# lora_repeter_2.net
KiCad netlist of a schematic drawn in EasyEDA Pro
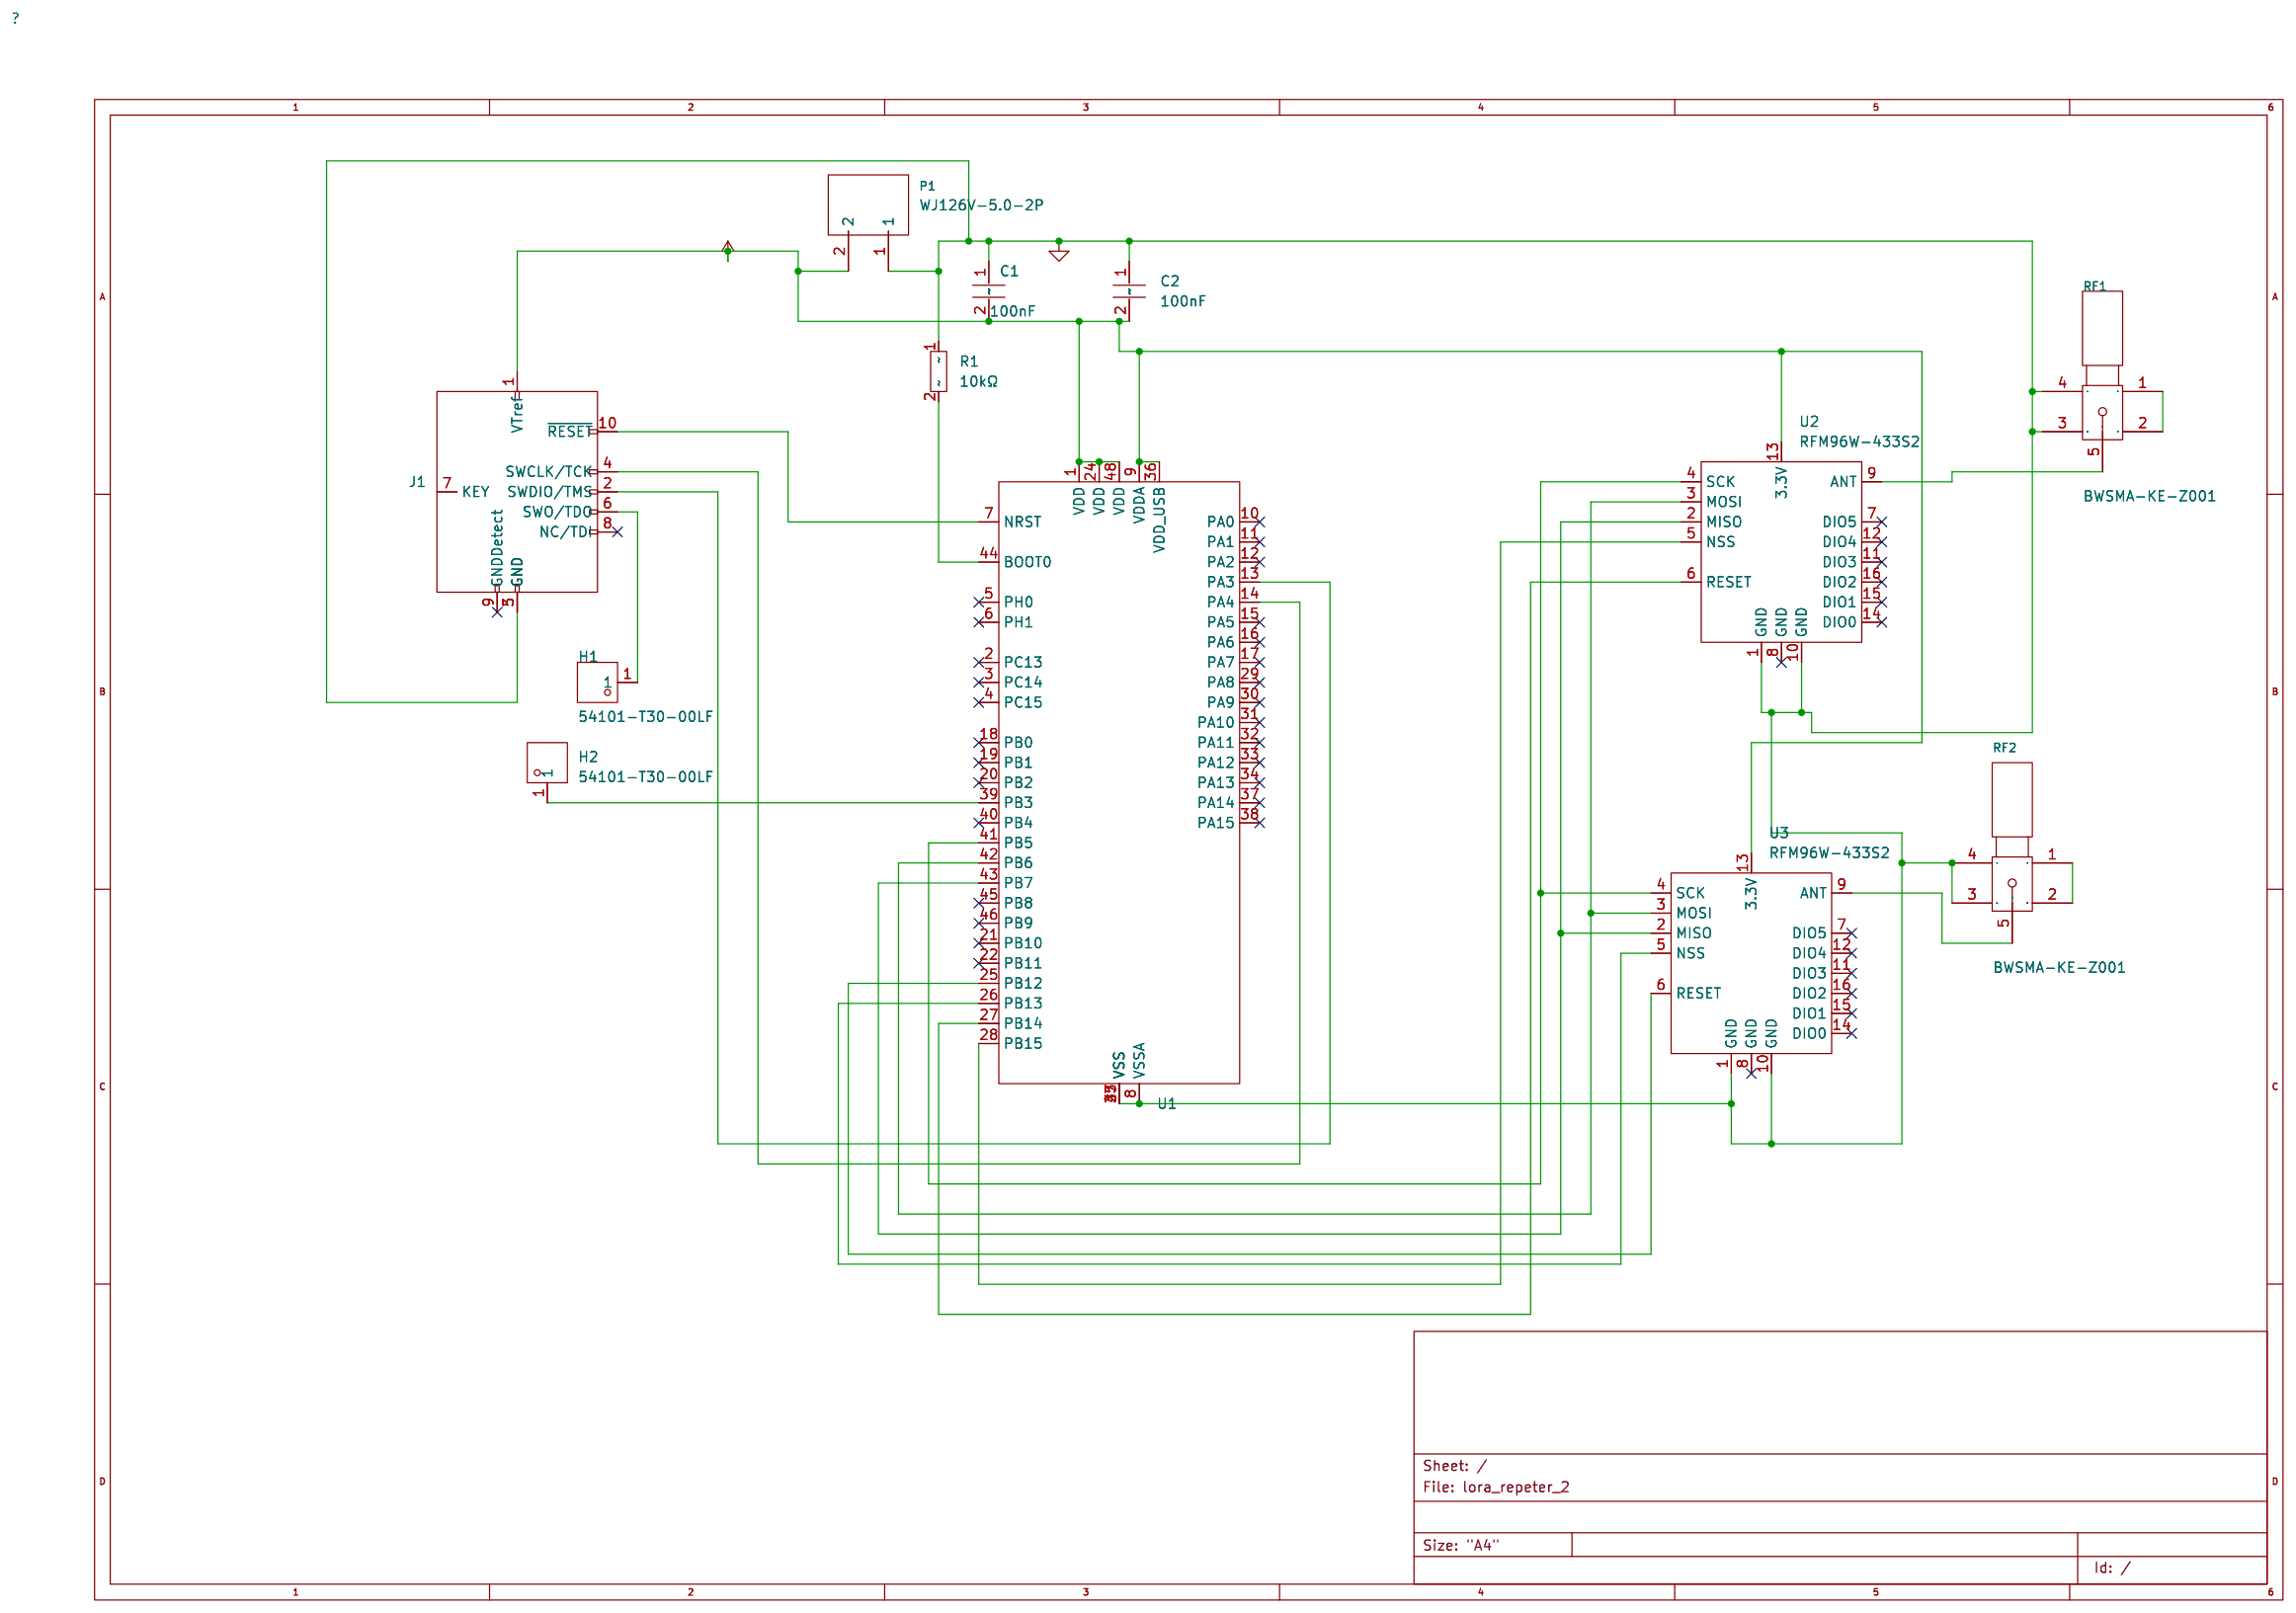
[diagram p0: schematic sheet]

(export (version "E")
  (design (tool "Eeschema 10.0.6"))
  (components
    (comp (ref "C1")
      (value "100nF")
      (fields
        (field (name "Manufacturer Part") "CC1H104ZC74D3F5O30MN")
        (field (name "Manufacturer") "Dersonic(德尔创)")
      )
      (libsource (lib "easyedapro") (part "Device_C"))
    )
    (comp (ref "C2")
      (value "100nF")
      (fields
        (field (name "Manufacturer Part") "CC1H104ZC74D3F5O30MN")
        (field (name "Manufacturer") "Dersonic(德尔创)")
      )
      (libsource (lib "easyedapro") (part "Device_C"))
    )
    (comp (ref "H1")
      (value "54101-T30-00LF")
      (footprint "easyedapro:HDR-TH_1P-P2.54-V-M")
      (fields (field (name "Manufacturer") "Amphenol"))
      (libsource (lib "easyedapro") (part "54101-T30-00LF"))
    )
    (comp (ref "H2")
      (value "54101-T30-00LF")
      (footprint "easyedapro:HDR-TH_1P-P2.54-V-M")
      (fields (field (name "Manufacturer") "Amphenol"))
      (libsource (lib "easyedapro") (part "54101-T30-00LF"))
    )
    (comp (ref "J1")
      (value "2.54-2*5P简牛")
      (fields (field (name "Manufacturer") "BOOMELE(博穆精密)"))
      (libsource (lib "easyedapro") (part "Connector_Conn_ARM_JTAG_SWD_10"))
    )
    (comp (ref "P1")
      (value "WJ126V-5.0-2P")
      (footprint "easyedapro:CONN-TH_WJ126V-5.0-2P")
      (fields (field (name "Manufacturer") "KANGNEX(康奈克斯电气)"))
      (libsource (lib "easyedapro") (part "WJ126V-5.0-2P"))
    )
    (comp (ref "R1")
      (value "10kΩ")
      (fields (field (name "Manufacturer Part") "MF1/4W-10KΩ±1% T") (field (name "Manufacturer") "CCO(千志电子)"))
      (libsource (lib "easyedapro") (part "Device_R"))
    )
    (comp (ref "RF1")
      (value "BWSMA-KE-Z001")
      (footprint "easyedapro:SMA-TH_BWSMA-KE-Z001")
      (fields (field (name "Manufacturer") "BAT WIRELESS(蝙蝠无线)"))
      (libsource (lib "easyedapro") (part "BWSMA-KE-Z001"))
    )
    (comp (ref "RF2")
      (value "BWSMA-KE-Z001")
      (footprint "easyedapro:SMA-TH_BWSMA-KE-Z001")
      (fields (field (name "Manufacturer") "BAT WIRELESS(蝙蝠无线)"))
      (libsource (lib "easyedapro") (part "BWSMA-KE-Z001"))
    )
    (comp (ref "U1")
      (value "STM32L072CBT6")
      (fields (field (name "Manufacturer") "ST(意法半导体)"))
      (libsource (lib "easyedapro") (part "MCU_ST_STM32L0_STM32L072CBTx"))
    )
    (comp (ref "U2") (value "RFM96W-433S2") (libsource (lib "easyedapro") (part "RF_Module_RFM96W-433S2")))
    (comp (ref "U3") (value "RFM96W-433S2") (libsource (lib "easyedapro") (part "RF_Module_RFM96W-433S2")))
  )
  (nets
    (net (code "1") (name "Net-(J1-SWCLK{slash}TCK)") (class "Default")
      (node (ref "J1") (pin "4") (pinfunction "SWCLK/TCK_4") (pintype "output"))
      (node (ref "U1") (pin "14") (pinfunction "PA4_14") (pintype "bidirectional"))
    )
    (net (code "2") (name "Net-(J1-SWDIO{slash}TMS)") (class "Default")
      (node (ref "J1") (pin "2") (pinfunction "SWDIO/TMS_2") (pintype "bidirectional"))
      (node (ref "U1") (pin "13") (pinfunction "PA3_13") (pintype "bidirectional"))
    )
    (net (code "3") (name "Net-(J1-SWO{slash}TDO)") (class "Default")
      (node (ref "H1") (pin "1") (pinfunction "1_1") (pintype "unspecified"))
      (node (ref "J1") (pin "6") (pinfunction "SWO/TDO_6") (pintype "input"))
    )
    (net (code "4") (name "Net-(J1-~{RESET})") (class "Default")
      (node (ref "J1") (pin "10") (pinfunction "~{RESET}_10") (pintype "unspecified"))
      (node (ref "U1") (pin "7") (pinfunction "NRST_7") (pintype "input"))
    )
    (net (code "5") (name "Net-(RF1-Pad1)") (class "Default")
      (node (ref "RF1") (pin "1") (pinfunction "1_1") (pintype "input"))
      (node (ref "RF1") (pin "2") (pinfunction "2_2") (pintype "input"))
    )
    (net (code "6") (name "Net-(RF2-Pad1)") (class "Default")
      (node (ref "RF2") (pin "1") (pinfunction "1_1") (pintype "input"))
      (node (ref "RF2") (pin "2") (pinfunction "2_2") (pintype "input"))
    )
    (net (code "7") (name "Net-(U1-BOOT0)") (class "Default")
      (node (ref "R1") (pin "2") (pinfunction "~_2") (pintype "unspecified"))
      (node (ref "U1") (pin "44") (pinfunction "BOOT0_44") (pintype "input"))
    )
    (net (code "8") (name "Net-(U1-PB3)") (class "Default")
      (node (ref "H2") (pin "1") (pinfunction "1_1") (pintype "unspecified"))
      (node (ref "U1") (pin "39") (pinfunction "PB3_39") (pintype "bidirectional"))
    )
    (net (code "9") (name "Net-(U1-PB5)") (class "Default")
      (node (ref "U1") (pin "41") (pinfunction "PB5_41") (pintype "bidirectional"))
      (node (ref "U2") (pin "4") (pinfunction "SCK_4") (pintype "input"))
      (node (ref "U3") (pin "4") (pinfunction "SCK_4") (pintype "input"))
    )
    (net (code "10") (name "Net-(U1-PB6)") (class "Default")
      (node (ref "U1") (pin "42") (pinfunction "PB6_42") (pintype "bidirectional"))
      (node (ref "U2") (pin "3") (pinfunction "MOSI_3") (pintype "input"))
      (node (ref "U3") (pin "3") (pinfunction "MOSI_3") (pintype "input"))
    )
    (net (code "11") (name "Net-(U1-PB7)") (class "Default")
      (node (ref "U1") (pin "43") (pinfunction "PB7_43") (pintype "bidirectional"))
      (node (ref "U2") (pin "2") (pinfunction "MISO_2") (pintype "output"))
      (node (ref "U3") (pin "2") (pinfunction "MISO_2") (pintype "output"))
    )
    (net (code "12") (name "Net-(U1-PB12)") (class "Default")
      (node (ref "U1") (pin "25") (pinfunction "PB12_25") (pintype "bidirectional"))
      (node (ref "U3") (pin "6") (pinfunction "RESET_6") (pintype "bidirectional"))
    )
    (net (code "13") (name "Net-(U1-PB13)") (class "Default")
      (node (ref "U1") (pin "26") (pinfunction "PB13_26") (pintype "bidirectional"))
      (node (ref "U3") (pin "5") (pinfunction "NSS_5") (pintype "input"))
    )
    (net (code "14") (name "Net-(U1-PB14)") (class "Default")
      (node (ref "U1") (pin "27") (pinfunction "PB14_27") (pintype "bidirectional"))
      (node (ref "U2") (pin "6") (pinfunction "RESET_6") (pintype "bidirectional"))
    )
    (net (code "15") (name "Net-(U1-PB15)") (class "Default")
      (node (ref "U1") (pin "28") (pinfunction "PB15_28") (pintype "bidirectional"))
      (node (ref "U2") (pin "5") (pinfunction "NSS_5") (pintype "input"))
    )
    (net (code "16") (name "Net-(U2-ANT)") (class "Default")
      (node (ref "RF1") (pin "5") (pinfunction "5_5") (pintype "input"))
      (node (ref "U2") (pin "9") (pinfunction "ANT_9") (pintype "bidirectional"))
    )
    (net (code "17") (name "Net-(U3-ANT)") (class "Default")
      (node (ref "RF2") (pin "5") (pinfunction "5_5") (pintype "input"))
      (node (ref "U3") (pin "9") (pinfunction "ANT_9") (pintype "bidirectional"))
    )
    (net (code "18") (name "POWER_+3.3V") (class "Default")
      (node (ref "C1") (pin "2") (pinfunction "~_2") (pintype "unspecified"))
      (node (ref "C2") (pin "2") (pinfunction "~_2") (pintype "unspecified"))
      (node (ref "J1") (pin "1") (pinfunction "VTref_1") (pintype "unspecified"))
      (node (ref "P1") (pin "2") (pinfunction "2_2") (pintype "input"))
      (node (ref "U1") (pin "1") (pinfunction "VDD_1") (pintype "unspecified"))
      (node (ref "U1") (pin "24") (pinfunction "VDD_24") (pintype "unspecified"))
      (node (ref "U1") (pin "36") (pinfunction "VDD_USB_36") (pintype "unspecified"))
      (node (ref "U1") (pin "48") (pinfunction "VDD_48") (pintype "unspecified"))
      (node (ref "U1") (pin "9") (pinfunction "VDDA_9") (pintype "unspecified"))
      (node (ref "U2") (pin "13") (pinfunction "3.3V_13") (pintype "unspecified"))
      (node (ref "U3") (pin "13") (pinfunction "3.3V_13") (pintype "unspecified"))
    )
    (net (code "19") (name "POWER_GND") (class "Default")
      (node (ref "C1") (pin "1") (pinfunction "~_1") (pintype "unspecified"))
      (node (ref "C2") (pin "1") (pinfunction "~_1") (pintype "unspecified"))
      (node (ref "J1") (pin "3") (pinfunction "GND_3") (pintype "unspecified"))
      (node (ref "J1") (pin "5") (pinfunction "GND_5") (pintype "unspecified"))
      (node (ref "P1") (pin "1") (pinfunction "1_1") (pintype "input"))
      (node (ref "R1") (pin "1") (pinfunction "~_1") (pintype "unspecified"))
      (node (ref "RF1") (pin "3") (pinfunction "3_3") (pintype "input"))
      (node (ref "RF1") (pin "4") (pinfunction "4_4") (pintype "input"))
      (node (ref "RF2") (pin "3") (pinfunction "3_3") (pintype "input"))
      (node (ref "RF2") (pin "4") (pinfunction "4_4") (pintype "input"))
      (node (ref "U1") (pin "23") (pinfunction "VSS_23") (pintype "unspecified"))
      (node (ref "U1") (pin "35") (pinfunction "VSS_35") (pintype "unspecified"))
      (node (ref "U1") (pin "47") (pinfunction "VSS_47") (pintype "unspecified"))
      (node (ref "U1") (pin "8") (pinfunction "VSSA_8") (pintype "unspecified"))
      (node (ref "U2") (pin "1") (pinfunction "GND_1") (pintype "unspecified"))
      (node (ref "U2") (pin "10") (pinfunction "GND_10") (pintype "unspecified"))
      (node (ref "U3") (pin "1") (pinfunction "GND_1") (pintype "unspecified"))
      (node (ref "U3") (pin "10") (pinfunction "GND_10") (pintype "unspecified"))
    )
    (net (code "20") (name "unconnected-(J1-GNDDetect-Pad9)") (class "Default")
      (node (ref "J1") (pin "9") (pinfunction "GNDDetect_9") (pintype "unspecified+no_connect"))
    )
    (net (code "21") (name "unconnected-(J1-KEY-Pad7)") (class "Default")
      (node (ref "J1") (pin "7") (pinfunction "KEY_7") (pintype "unspecified"))
    )
    (net (code "22") (name "unconnected-(J1-NC{slash}TDI-Pad8)") (class "Default")
      (node (ref "J1") (pin "8") (pinfunction "NC/TDI_8") (pintype "output+no_connect"))
    )
    (net (code "23") (name "unconnected-(U1-PA0-Pad10)") (class "Default")
      (node (ref "U1") (pin "10") (pinfunction "PA0_10") (pintype "bidirectional+no_connect"))
    )
    (net (code "24") (name "unconnected-(U1-PA1-Pad11)") (class "Default")
      (node (ref "U1") (pin "11") (pinfunction "PA1_11") (pintype "bidirectional+no_connect"))
    )
    (net (code "25") (name "unconnected-(U1-PA2-Pad12)") (class "Default")
      (node (ref "U1") (pin "12") (pinfunction "PA2_12") (pintype "bidirectional+no_connect"))
    )
    (net (code "26") (name "unconnected-(U1-PA5-Pad15)") (class "Default")
      (node (ref "U1") (pin "15") (pinfunction "PA5_15") (pintype "bidirectional+no_connect"))
    )
    (net (code "27") (name "unconnected-(U1-PA6-Pad16)") (class "Default")
      (node (ref "U1") (pin "16") (pinfunction "PA6_16") (pintype "bidirectional+no_connect"))
    )
    (net (code "28") (name "unconnected-(U1-PA7-Pad17)") (class "Default")
      (node (ref "U1") (pin "17") (pinfunction "PA7_17") (pintype "bidirectional+no_connect"))
    )
    (net (code "29") (name "unconnected-(U1-PA8-Pad29)") (class "Default")
      (node (ref "U1") (pin "29") (pinfunction "PA8_29") (pintype "bidirectional+no_connect"))
    )
    (net (code "30") (name "unconnected-(U1-PA9-Pad30)") (class "Default")
      (node (ref "U1") (pin "30") (pinfunction "PA9_30") (pintype "bidirectional+no_connect"))
    )
    (net (code "31") (name "unconnected-(U1-PA10-Pad31)") (class "Default")
      (node (ref "U1") (pin "31") (pinfunction "PA10_31") (pintype "bidirectional+no_connect"))
    )
    (net (code "32") (name "unconnected-(U1-PA11-Pad32)") (class "Default")
      (node (ref "U1") (pin "32") (pinfunction "PA11_32") (pintype "bidirectional+no_connect"))
    )
    (net (code "33") (name "unconnected-(U1-PA12-Pad33)") (class "Default")
      (node (ref "U1") (pin "33") (pinfunction "PA12_33") (pintype "bidirectional+no_connect"))
    )
    (net (code "34") (name "unconnected-(U1-PA13-Pad34)") (class "Default")
      (node (ref "U1") (pin "34") (pinfunction "PA13_34") (pintype "bidirectional+no_connect"))
    )
    (net (code "35") (name "unconnected-(U1-PA14-Pad37)") (class "Default")
      (node (ref "U1") (pin "37") (pinfunction "PA14_37") (pintype "bidirectional+no_connect"))
    )
    (net (code "36") (name "unconnected-(U1-PA15-Pad38)") (class "Default")
      (node (ref "U1") (pin "38") (pinfunction "PA15_38") (pintype "bidirectional+no_connect"))
    )
    (net (code "37") (name "unconnected-(U1-PB0-Pad18)") (class "Default")
      (node (ref "U1") (pin "18") (pinfunction "PB0_18") (pintype "bidirectional+no_connect"))
    )
    (net (code "38") (name "unconnected-(U1-PB1-Pad19)") (class "Default")
      (node (ref "U1") (pin "19") (pinfunction "PB1_19") (pintype "bidirectional+no_connect"))
    )
    (net (code "39") (name "unconnected-(U1-PB2-Pad20)") (class "Default")
      (node (ref "U1") (pin "20") (pinfunction "PB2_20") (pintype "bidirectional+no_connect"))
    )
    (net (code "40") (name "unconnected-(U1-PB4-Pad40)") (class "Default")
      (node (ref "U1") (pin "40") (pinfunction "PB4_40") (pintype "bidirectional+no_connect"))
    )
    (net (code "41") (name "unconnected-(U1-PB8-Pad45)") (class "Default")
      (node (ref "U1") (pin "45") (pinfunction "PB8_45") (pintype "bidirectional+no_connect"))
    )
    (net (code "42") (name "unconnected-(U1-PB9-Pad46)") (class "Default")
      (node (ref "U1") (pin "46") (pinfunction "PB9_46") (pintype "bidirectional+no_connect"))
    )
    (net (code "43") (name "unconnected-(U1-PB10-Pad21)") (class "Default")
      (node (ref "U1") (pin "21") (pinfunction "PB10_21") (pintype "bidirectional+no_connect"))
    )
    (net (code "44") (name "unconnected-(U1-PB11-Pad22)") (class "Default")
      (node (ref "U1") (pin "22") (pinfunction "PB11_22") (pintype "bidirectional+no_connect"))
    )
    (net (code "45") (name "unconnected-(U1-PC13-Pad2)") (class "Default")
      (node (ref "U1") (pin "2") (pinfunction "PC13_2") (pintype "bidirectional+no_connect"))
    )
    (net (code "46") (name "unconnected-(U1-PC14-Pad3)") (class "Default")
      (node (ref "U1") (pin "3") (pinfunction "PC14_3") (pintype "bidirectional+no_connect"))
    )
    (net (code "47") (name "unconnected-(U1-PC15-Pad4)") (class "Default")
      (node (ref "U1") (pin "4") (pinfunction "PC15_4") (pintype "bidirectional+no_connect"))
    )
    (net (code "48") (name "unconnected-(U1-PH0-Pad5)") (class "Default")
      (node (ref "U1") (pin "5") (pinfunction "PH0_5") (pintype "bidirectional+no_connect"))
    )
    (net (code "49") (name "unconnected-(U1-PH1-Pad6)") (class "Default")
      (node (ref "U1") (pin "6") (pinfunction "PH1_6") (pintype "bidirectional+no_connect"))
    )
    (net (code "50") (name "unconnected-(U2-DIO0-Pad14)") (class "Default")
      (node (ref "U2") (pin "14") (pinfunction "DIO0_14") (pintype "bidirectional+no_connect"))
    )
    (net (code "51") (name "unconnected-(U2-DIO1-Pad15)") (class "Default")
      (node (ref "U2") (pin "15") (pinfunction "DIO1_15") (pintype "bidirectional+no_connect"))
    )
    (net (code "52") (name "unconnected-(U2-DIO2-Pad16)") (class "Default")
      (node (ref "U2") (pin "16") (pinfunction "DIO2_16") (pintype "bidirectional+no_connect"))
    )
    (net (code "53") (name "unconnected-(U2-DIO3-Pad11)") (class "Default")
      (node (ref "U2") (pin "11") (pinfunction "DIO3_11") (pintype "bidirectional+no_connect"))
    )
    (net (code "54") (name "unconnected-(U2-DIO4-Pad12)") (class "Default")
      (node (ref "U2") (pin "12") (pinfunction "DIO4_12") (pintype "bidirectional+no_connect"))
    )
    (net (code "55") (name "unconnected-(U2-DIO5-Pad7)") (class "Default")
      (node (ref "U2") (pin "7") (pinfunction "DIO5_7") (pintype "bidirectional+no_connect"))
    )
    (net (code "56") (name "unconnected-(U2-GND-Pad8)") (class "Default")
      (node (ref "U2") (pin "8") (pinfunction "GND_8") (pintype "unspecified+no_connect"))
    )
    (net (code "57") (name "unconnected-(U3-DIO0-Pad14)") (class "Default")
      (node (ref "U3") (pin "14") (pinfunction "DIO0_14") (pintype "bidirectional+no_connect"))
    )
    (net (code "58") (name "unconnected-(U3-DIO1-Pad15)") (class "Default")
      (node (ref "U3") (pin "15") (pinfunction "DIO1_15") (pintype "bidirectional+no_connect"))
    )
    (net (code "59") (name "unconnected-(U3-DIO2-Pad16)") (class "Default")
      (node (ref "U3") (pin "16") (pinfunction "DIO2_16") (pintype "bidirectional+no_connect"))
    )
    (net (code "60") (name "unconnected-(U3-DIO3-Pad11)") (class "Default")
      (node (ref "U3") (pin "11") (pinfunction "DIO3_11") (pintype "bidirectional+no_connect"))
    )
    (net (code "61") (name "unconnected-(U3-DIO4-Pad12)") (class "Default")
      (node (ref "U3") (pin "12") (pinfunction "DIO4_12") (pintype "bidirectional+no_connect"))
    )
    (net (code "62") (name "unconnected-(U3-DIO5-Pad7)") (class "Default")
      (node (ref "U3") (pin "7") (pinfunction "DIO5_7") (pintype "bidirectional+no_connect"))
    )
    (net (code "63") (name "unconnected-(U3-GND-Pad8)") (class "Default")
      (node (ref "U3") (pin "8") (pinfunction "GND_8") (pintype "unspecified+no_connect"))
    )
  )
)
